# Color-Experimentation.net
KiCad netlist of a schematic drawn in EAGLE
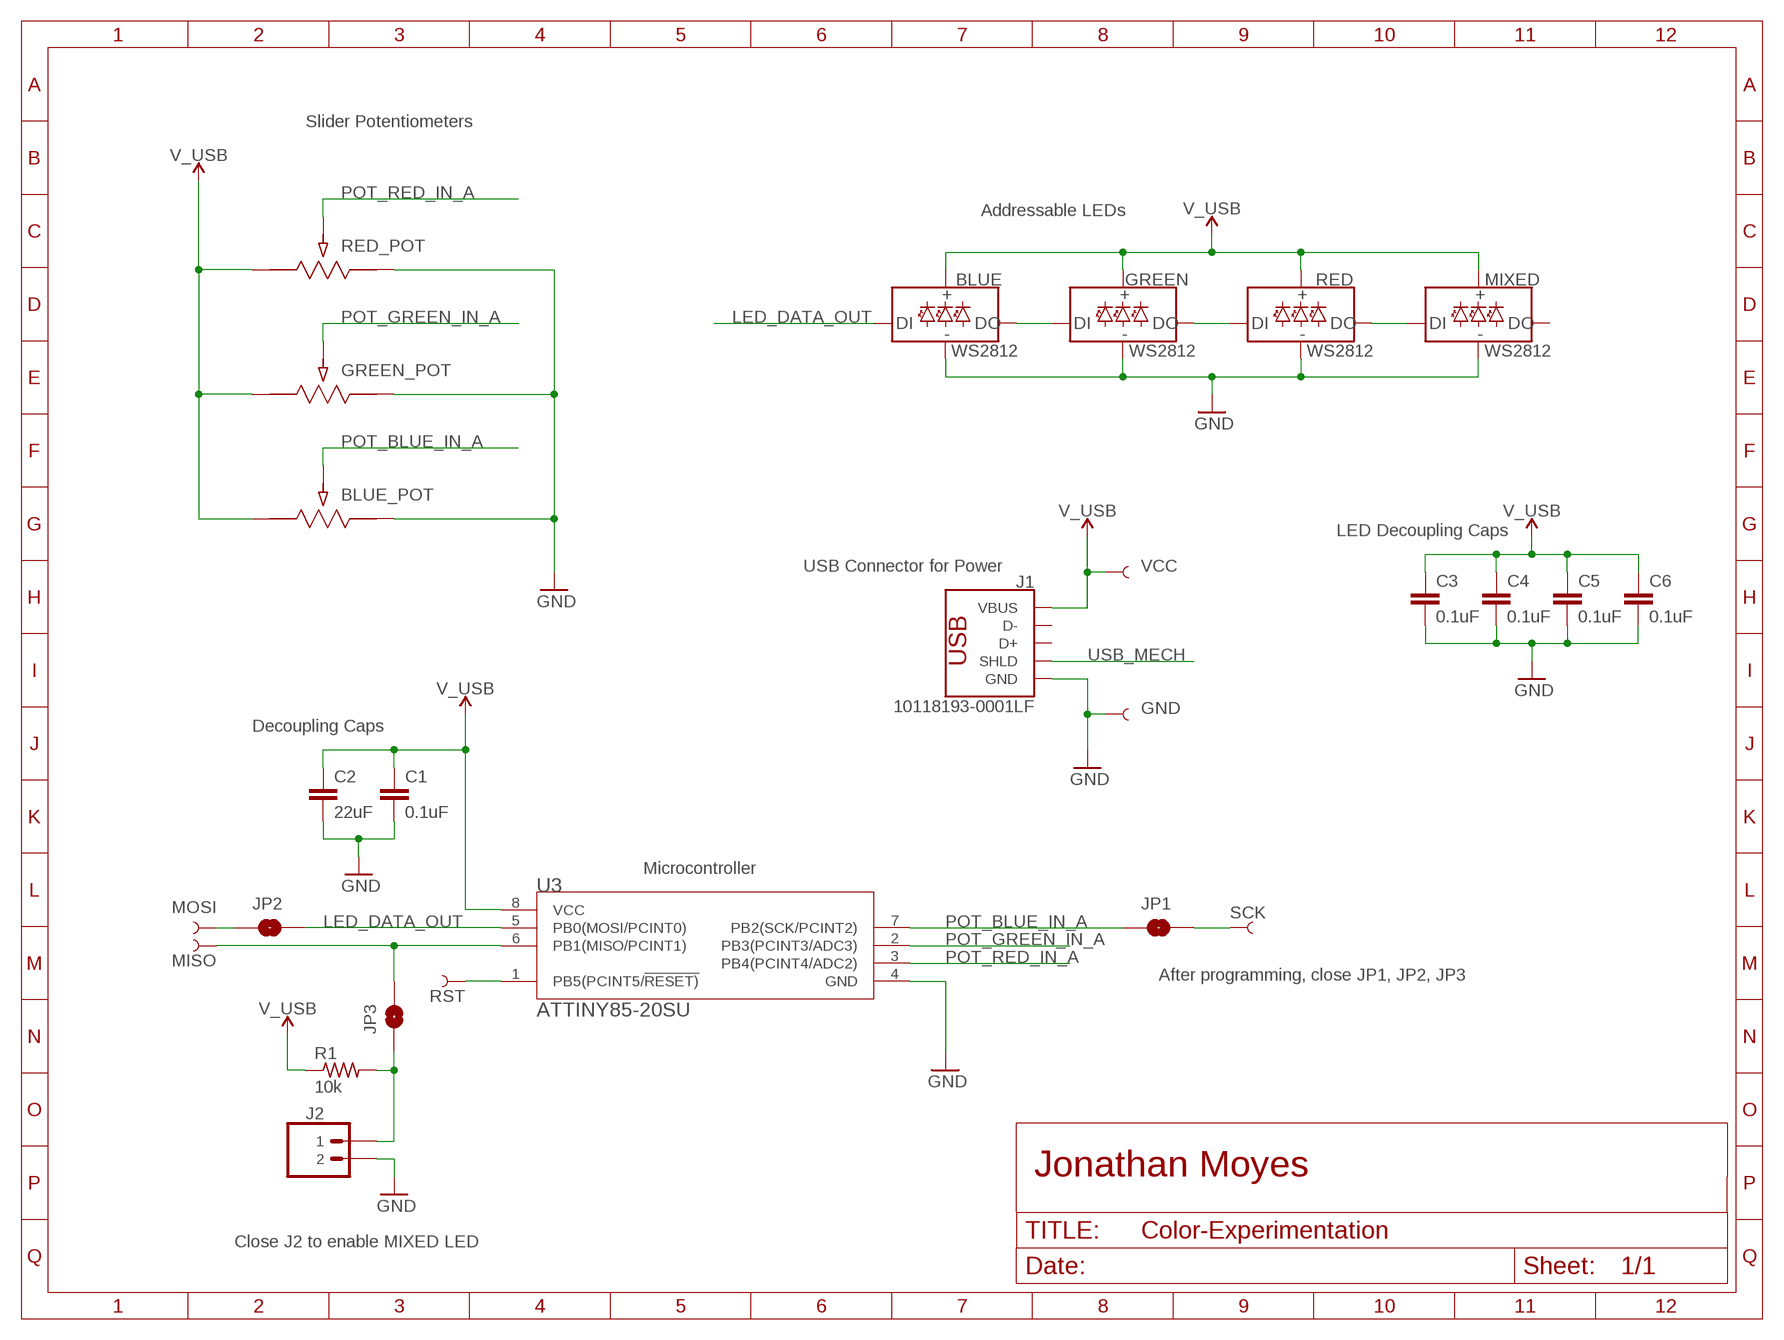
[diagram p0: schematic, sheet 1]

(export (version "E")
  (design (tool "Eeschema 10.0.6"))
  (components
    (comp (ref "BLUE")
      (value "WS2812")
      (footprint "eagle-import:WS2812-5X5-4PIN")
      (fields (field (name "MFG") "SparkFun.com") (field (name "MPN") "WS2812B 5050"))
      (libsource (lib "eagle-import") (part "WS2812_5050"))
    )
    (comp (ref "BLUE_POT")
      (value "10k")
      (footprint "eagle-import:POT_PTA2043")
      (fields (field (name "MFG") "Bourns Inc.") (field (name "MPN") "PTA2043-2015DPB103"))
      (libsource (lib "eagle-import") (part "PTA2043-2015DPB103"))
    )
    (comp (ref "C1")
      (value "0.1uF")
      (footprint "eagle-import:CAP_0603")
      (fields (field (name "MFG") "Samsung Electro-Mechanics") (field (name "MPN") "CL10B104KA8WPNC"))
      (libsource (lib "eagle-import") (part "CAP_0.1UF_25V_X7R-0603"))
    )
    (comp (ref "C2")
      (value "22uF")
      (footprint "eagle-import:C0603")
      (fields (field (name "MFG") "Samsung Electro-Mechanics") (field (name "MPN") "CL21A226MOQNNNE"))
      (libsource (lib "eagle-import") (part "CAP_22UF_16V_X5R-0603"))
    )
    (comp (ref "C3")
      (value "0.1uF")
      (footprint "eagle-import:CAP_0603")
      (fields (field (name "MFG") "Samsung Electro-Mechanics") (field (name "MPN") "CL10B104KA8WPNC"))
      (libsource (lib "eagle-import") (part "CAP_0.1UF_25V_X7R-0603"))
    )
    (comp (ref "C4")
      (value "0.1uF")
      (footprint "eagle-import:CAP_0603")
      (fields (field (name "MFG") "Samsung Electro-Mechanics") (field (name "MPN") "CL10B104KA8WPNC"))
      (libsource (lib "eagle-import") (part "CAP_0.1UF_25V_X7R-0603"))
    )
    (comp (ref "C5")
      (value "0.1uF")
      (footprint "eagle-import:CAP_0603")
      (fields (field (name "MFG") "Samsung Electro-Mechanics") (field (name "MPN") "CL10B104KA8WPNC"))
      (libsource (lib "eagle-import") (part "CAP_0.1UF_25V_X7R-0603"))
    )
    (comp (ref "C6")
      (value "0.1uF")
      (footprint "eagle-import:CAP_0603")
      (fields (field (name "MFG") "Samsung Electro-Mechanics") (field (name "MPN") "CL10B104KA8WPNC"))
      (libsource (lib "eagle-import") (part "CAP_0.1UF_25V_X7R-0603"))
    )
    (comp (ref "GND")
      (value "TEST-POINT40MIL")
      (footprint "eagle-import:TESTPOINT_40MIL_ROUND")
      (libsource (lib "eagle-import") (part "TEST-POINT40MIL"))
    )
    (comp (ref "GREEN")
      (value "WS2812")
      (footprint "eagle-import:WS2812-5X5-4PIN")
      (fields (field (name "MFG") "SparkFun.com") (field (name "MPN") "WS2812B 5050"))
      (libsource (lib "eagle-import") (part "WS2812_5050"))
    )
    (comp (ref "GREEN_POT")
      (value "10k")
      (footprint "eagle-import:POT_PTA2043")
      (fields (field (name "MFG") "Bourns Inc.") (field (name "MPN") "PTA2043-2015DPB103"))
      (libsource (lib "eagle-import") (part "PTA2043-2015DPB103"))
    )
    (comp (ref "J1")
      (value "10118193-0001LF")
      (footprint "eagle-import:CONN_10118193-0001LF_AMP")
      (fields (field (name "MFG") "Amphenol ICC"))
      (libsource (lib "eagle-import") (part "10118193-0001LF"))
    )
    (comp (ref "J2")
      (value "CONN_02")
      (footprint "eagle-import:1X02")
      (fields (field (name "MFG") "Amazon.com") (field (name "MPN") "B07PWZ6G9G"))
      (libsource (lib "eagle-import") (part "CONN_02"))
    )
    (comp (ref "JP1")
      (value "JUMPER-SMT_2_NO_SILK")
      (footprint "eagle-import:SMT-JUMPER_2_NO_SILK")
      (libsource (lib "eagle-import") (part "JUMPER-SMT_2_NO_SILK"))
    )
    (comp (ref "JP2")
      (value "JUMPER-SMT_2_NO_SILK")
      (footprint "eagle-import:SMT-JUMPER_2_NO_SILK")
      (libsource (lib "eagle-import") (part "JUMPER-SMT_2_NO_SILK"))
    )
    (comp (ref "JP3")
      (value "JUMPER-SMT_2_NO_SILK")
      (footprint "eagle-import:SMT-JUMPER_2_NO_SILK")
      (libsource (lib "eagle-import") (part "JUMPER-SMT_2_NO_SILK"))
    )
    (comp (ref "MISO")
      (value "TEST-POINT40MIL")
      (footprint "eagle-import:TESTPOINT_40MIL_ROUND")
      (libsource (lib "eagle-import") (part "TEST-POINT40MIL"))
    )
    (comp (ref "MIXED")
      (value "WS2812")
      (footprint "eagle-import:WS2812-5X5-4PIN")
      (fields (field (name "MFG") "SparkFun.com") (field (name "MPN") "WS2812B 5050"))
      (libsource (lib "eagle-import") (part "WS2812_5050"))
    )
    (comp (ref "MOSI")
      (value "TEST-POINT40MIL")
      (footprint "eagle-import:TESTPOINT_40MIL_ROUND")
      (libsource (lib "eagle-import") (part "TEST-POINT40MIL"))
    )
    (comp (ref "R1")
      (value "10k")
      (footprint "eagle-import:R0603")
      (fields (field (name "MFG") "Yageo") (field (name "MPN") "RC0603FR-0710KL"))
      (libsource (lib "eagle-import") (part "RES_10K_1%R0603"))
    )
    (comp (ref "RED")
      (value "WS2812")
      (footprint "eagle-import:WS2812-5X5-4PIN")
      (fields (field (name "MFG") "SparkFun.com") (field (name "MPN") "WS2812B 5050"))
      (libsource (lib "eagle-import") (part "WS2812_5050"))
    )
    (comp (ref "RED_POT")
      (value "10k")
      (footprint "eagle-import:POT_PTA2043")
      (fields (field (name "MFG") "Bourns Inc.") (field (name "MPN") "PTA2043-2015DPB103"))
      (libsource (lib "eagle-import") (part "PTA2043-2015DPB103"))
    )
    (comp (ref "RST")
      (value "TEST-POINT40MIL")
      (footprint "eagle-import:TESTPOINT_40MIL_ROUND")
      (libsource (lib "eagle-import") (part "TEST-POINT40MIL"))
    )
    (comp (ref "SCK")
      (value "TEST-POINT40MIL")
      (footprint "eagle-import:TESTPOINT_40MIL_ROUND")
      (libsource (lib "eagle-import") (part "TEST-POINT40MIL"))
    )
    (comp (ref "U3")
      (value "ATTINY85-20SU")
      (footprint "eagle-import:SOIC127P798X216-8N")
      (fields (field (name "DIGI-KEY_PART_NUMBER") "ATTINY85-20SU-ND") (field (name "MF") "Microchip"))
      (libsource (lib "eagle-import") (part "ATTINY85-20SU"))
    )
    (comp (ref "VCC")
      (value "TEST-POINT40MIL")
      (footprint "eagle-import:TESTPOINT_40MIL_ROUND")
      (libsource (lib "eagle-import") (part "TEST-POINT40MIL"))
    )
  )
  (nets
    (net (code "1") (name "/LED_DATA_OUT") (class "Default")
      (node (ref "BLUE") (pin "DI") (pinfunction "DI_DI") (pintype "bidirectional"))
      (node (ref "JP2") (pin "2") (pinfunction "2_2") (pintype "passive"))
      (node (ref "U3") (pin "5") (pinfunction "PB0(MOSI/PCINT0)_5") (pintype "passive"))
    )
    (net (code "2") (name "/POT_BLUE_IN_A") (class "Default")
      (node (ref "BLUE_POT") (pin "WIPER") (pinfunction "2_WIPER") (pintype "passive"))
      (node (ref "JP1") (pin "1") (pinfunction "1_1") (pintype "passive"))
      (node (ref "U3") (pin "7") (pinfunction "PB2(SCK/PCINT2)_7") (pintype "passive"))
    )
    (net (code "3") (name "/POT_GREEN_IN_A") (class "Default")
      (node (ref "GREEN_POT") (pin "WIPER") (pinfunction "2_WIPER") (pintype "passive"))
      (node (ref "U3") (pin "2") (pinfunction "PB3(PCINT3/ADC3)_2") (pintype "passive"))
    )
    (net (code "4") (name "/POT_RED_IN_A") (class "Default")
      (node (ref "RED_POT") (pin "WIPER") (pinfunction "2_WIPER") (pintype "passive"))
      (node (ref "U3") (pin "3") (pinfunction "PB4(PCINT4/ADC2)_3") (pintype "passive"))
    )
    (net (code "5") (name "/USB_MECH") (class "Default")
      (node (ref "J1") (pin "4") (pinfunction "SHLD_4") (pintype "bidirectional"))
      (node (ref "J1") (pin "6") (pinfunction "SHLD_6") (pintype "bidirectional"))
      (node (ref "J1") (pin "7") (pinfunction "SHLD_7") (pintype "bidirectional"))
      (node (ref "J1") (pin "8") (pinfunction "SHLD_8") (pintype "bidirectional"))
      (node (ref "J1") (pin "9") (pinfunction "SHLD_9") (pintype "bidirectional"))
      (node (ref "J1") (pin "S_1") (pinfunction "SHLD_S_1") (pintype "bidirectional"))
      (node (ref "J1") (pin "S_1_H1") (pinfunction "SHLD_S_1_H1") (pintype "bidirectional"))
      (node (ref "J1") (pin "S_1_H2") (pinfunction "SHLD_S_1_H2") (pintype "bidirectional"))
      (node (ref "J1") (pin "S_2") (pinfunction "SHLD_S_2") (pintype "bidirectional"))
      (node (ref "J1") (pin "S_2_H1") (pinfunction "SHLD_S_2_H1") (pintype "bidirectional"))
      (node (ref "J1") (pin "S_2_H2") (pinfunction "SHLD_S_2_H2") (pintype "bidirectional"))
    )
    (net (code "6") (name "GND") (class "Default")
      (node (ref "BLUE") (pin "GND") (pinfunction "GND_GND") (pintype "bidirectional"))
      (node (ref "BLUE_POT") (pin "3") (pinfunction "3_3") (pintype "passive"))
      (node (ref "C1") (pin "2") (pinfunction "2_2") (pintype "passive"))
      (node (ref "C2") (pin "2") (pinfunction "2_2") (pintype "passive"))
      (node (ref "C3") (pin "2") (pinfunction "2_2") (pintype "passive"))
      (node (ref "C4") (pin "2") (pinfunction "2_2") (pintype "passive"))
      (node (ref "C5") (pin "2") (pinfunction "2_2") (pintype "passive"))
      (node (ref "C6") (pin "2") (pinfunction "2_2") (pintype "passive"))
      (node (ref "GND") (pin "P$1") (pinfunction "1_P$1") (pintype "bidirectional"))
      (node (ref "GREEN") (pin "GND") (pinfunction "GND_GND") (pintype "bidirectional"))
      (node (ref "GREEN_POT") (pin "3") (pinfunction "3_3") (pintype "passive"))
      (node (ref "J1") (pin "5") (pinfunction "GND_5") (pintype "power_in"))
      (node (ref "J2") (pin "1") (pinfunction "2_1") (pintype "passive"))
      (node (ref "MIXED") (pin "GND") (pinfunction "GND_GND") (pintype "bidirectional"))
      (node (ref "RED") (pin "GND") (pinfunction "GND_GND") (pintype "bidirectional"))
      (node (ref "RED_POT") (pin "3") (pinfunction "3_3") (pintype "passive"))
      (node (ref "U3") (pin "4") (pinfunction "GND_4") (pintype "passive"))
    )
    (net (code "7") (name "Net-(BLUE-PadDO)") (class "Default")
      (node (ref "BLUE") (pin "DO") (pinfunction "DO_DO") (pintype "bidirectional"))
      (node (ref "GREEN") (pin "DI") (pinfunction "DI_DI") (pintype "bidirectional"))
    )
    (net (code "8") (name "Net-(GREEN-PadDO)") (class "Default")
      (node (ref "GREEN") (pin "DO") (pinfunction "DO_DO") (pintype "bidirectional"))
      (node (ref "RED") (pin "DI") (pinfunction "DI_DI") (pintype "bidirectional"))
    )
    (net (code "9") (name "Net-(J2-1)") (class "Default")
      (node (ref "J2") (pin "2") (pinfunction "1_2") (pintype "passive"))
      (node (ref "JP3") (pin "1") (pinfunction "1_1") (pintype "passive"))
      (node (ref "R1") (pin "2") (pinfunction "2_2") (pintype "passive"))
    )
    (net (code "10") (name "Net-(MISO-1)") (class "Default")
      (node (ref "JP3") (pin "2") (pinfunction "2_2") (pintype "passive"))
      (node (ref "MISO") (pin "P$1") (pinfunction "1_P$1") (pintype "bidirectional"))
      (node (ref "U3") (pin "6") (pinfunction "PB1(MISO/PCINT1)_6") (pintype "passive"))
    )
    (net (code "11") (name "Net-(MIXED-PadDI)") (class "Default")
      (node (ref "MIXED") (pin "DI") (pinfunction "DI_DI") (pintype "bidirectional"))
      (node (ref "RED") (pin "DO") (pinfunction "DO_DO") (pintype "bidirectional"))
    )
    (net (code "12") (name "Net-(MOSI-1)") (class "Default")
      (node (ref "JP2") (pin "1") (pinfunction "1_1") (pintype "passive"))
      (node (ref "MOSI") (pin "P$1") (pinfunction "1_P$1") (pintype "bidirectional"))
    )
    (net (code "13") (name "Net-(RST-1)") (class "Default")
      (node (ref "RST") (pin "P$1") (pinfunction "1_P$1") (pintype "bidirectional"))
      (node (ref "U3") (pin "1") (pinfunction "PB5(PCINT5/~{RESET})_1") (pintype "passive"))
    )
    (net (code "14") (name "Net-(SCK-1)") (class "Default")
      (node (ref "JP1") (pin "2") (pinfunction "2_2") (pintype "passive"))
      (node (ref "SCK") (pin "P$1") (pinfunction "1_P$1") (pintype "bidirectional"))
    )
    (net (code "15") (name "V_USB") (class "Default")
      (node (ref "BLUE") (pin "VCC") (pinfunction "VCC_VCC") (pintype "bidirectional"))
      (node (ref "BLUE_POT") (pin "1") (pinfunction "1_1") (pintype "passive"))
      (node (ref "C1") (pin "1") (pinfunction "1_1") (pintype "passive"))
      (node (ref "C2") (pin "1") (pinfunction "1_1") (pintype "passive"))
      (node (ref "C3") (pin "1") (pinfunction "1_1") (pintype "passive"))
      (node (ref "C4") (pin "1") (pinfunction "1_1") (pintype "passive"))
      (node (ref "C5") (pin "1") (pinfunction "1_1") (pintype "passive"))
      (node (ref "C6") (pin "1") (pinfunction "1_1") (pintype "passive"))
      (node (ref "GREEN") (pin "VCC") (pinfunction "VCC_VCC") (pintype "bidirectional"))
      (node (ref "GREEN_POT") (pin "1") (pinfunction "1_1") (pintype "passive"))
      (node (ref "J1") (pin "1") (pinfunction "VBUS_1") (pintype "power_in"))
      (node (ref "MIXED") (pin "VCC") (pinfunction "VCC_VCC") (pintype "bidirectional"))
      (node (ref "R1") (pin "1") (pinfunction "1_1") (pintype "passive"))
      (node (ref "RED") (pin "VCC") (pinfunction "VCC_VCC") (pintype "bidirectional"))
      (node (ref "RED_POT") (pin "1") (pinfunction "1_1") (pintype "passive"))
      (node (ref "U3") (pin "8") (pinfunction "VCC_8") (pintype "passive"))
      (node (ref "VCC") (pin "P$1") (pinfunction "1_P$1") (pintype "bidirectional"))
    )
    (net (code "16") (name "unconnected-(J1-D+-Pad3)") (class "Default")
      (node (ref "J1") (pin "3") (pinfunction "D+_3") (pintype "bidirectional"))
    )
    (net (code "17") (name "unconnected-(J1-D--Pad2)") (class "Default")
      (node (ref "J1") (pin "2") (pinfunction "D-_2") (pintype "bidirectional"))
    )
    (net (code "18") (name "unconnected-(MIXED-PadDO)") (class "Default")
      (node (ref "MIXED") (pin "DO") (pinfunction "DO_DO") (pintype "bidirectional"))
    )
  )
)
